# singleBlinkCricut.net
KiCad netlist of a schematic drawn in EAGLE
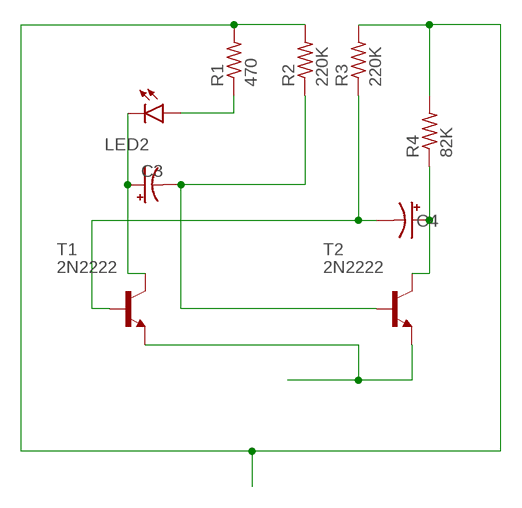
[diagram p0: schematic, sheet 1]

(export (version "E")
  (design (tool "Eeschema 10.0.6"))
  (components
    (comp (ref "C3")
      (value "CPOL-USE2.5-6")
      (footprint "eagle-import:E2,5-6")
      (libsource (lib "eagle-import") (part "CPOL-USE2.5-6"))
    )
    (comp (ref "C4")
      (value "CPOL-USE2.5-6")
      (footprint "eagle-import:E2,5-6")
      (libsource (lib "eagle-import") (part "CPOL-USE2.5-6"))
    )
    (comp (ref "LED2")
      (value "LED10MM")
      (footprint "eagle-import:LED10MM")
      (libsource (lib "eagle-import") (part "LED10MM"))
    )
    (comp (ref "R1")
      (value "470")
      (footprint "eagle-import:0411_12")
      (libsource (lib "eagle-import") (part "R-US_0411/12"))
    )
    (comp (ref "R2")
      (value "220K")
      (footprint "eagle-import:0411_12")
      (libsource (lib "eagle-import") (part "R-US_0411/12"))
    )
    (comp (ref "R3")
      (value "220K")
      (footprint "eagle-import:0411_12")
      (libsource (lib "eagle-import") (part "R-US_0411/12"))
    )
    (comp (ref "R4")
      (value "82K")
      (footprint "eagle-import:0411_12")
      (libsource (lib "eagle-import") (part "R-US_0411/12"))
    )
    (comp (ref "T1")
      (value "2N2222")
      (footprint "eagle-import:TO92-EBC-OVAL")
      (libsource (lib "eagle-import") (part "2N2222"))
    )
    (comp (ref "T2")
      (value "2N2222")
      (footprint "eagle-import:TO92-EBC-OVAL")
      (libsource (lib "eagle-import") (part "2N2222"))
    )
  )
  (nets
    (net (code "1") (name "Net-(C3-Pad-)") (class "Default")
      (node (ref "C3") (pin "-") (pinfunction "-_-") (pintype "passive"))
      (node (ref "R2") (pin "1") (pinfunction "1_1") (pintype "passive"))
      (node (ref "T2") (pin "B") (pinfunction "B_B") (pintype "passive"))
    )
    (net (code "2") (name "Net-(C4-Pad+)") (class "Default")
      (node (ref "C4") (pin "+") (pinfunction "+_+") (pintype "passive"))
      (node (ref "R4") (pin "1") (pinfunction "1_1") (pintype "passive"))
      (node (ref "T2") (pin "C") (pinfunction "C_C") (pintype "passive"))
    )
    (net (code "3") (name "Net-(C4-Pad-)") (class "Default")
      (node (ref "C4") (pin "-") (pinfunction "-_-") (pintype "passive"))
      (node (ref "R3") (pin "1") (pinfunction "1_1") (pintype "passive"))
      (node (ref "T1") (pin "B") (pinfunction "B_B") (pintype "passive"))
    )
    (net (code "4") (name "Net-(LED2-C)") (class "Default")
      (node (ref "C3") (pin "+") (pinfunction "+_+") (pintype "passive"))
      (node (ref "LED2") (pin "K") (pinfunction "C_K") (pintype "passive"))
      (node (ref "T1") (pin "C") (pinfunction "C_C") (pintype "passive"))
    )
    (net (code "5") (name "Net-(LED2-PadA)") (class "Default")
      (node (ref "LED2") (pin "A") (pinfunction "A_A") (pintype "passive"))
      (node (ref "R1") (pin "1") (pinfunction "1_1") (pintype "passive"))
    )
    (net (code "6") (name "Net-(R1-Pad2)") (class "Default")
      (node (ref "R1") (pin "2") (pinfunction "2_2") (pintype "passive"))
      (node (ref "R2") (pin "2") (pinfunction "2_2") (pintype "passive"))
      (node (ref "R3") (pin "2") (pinfunction "2_2") (pintype "passive"))
      (node (ref "R4") (pin "2") (pinfunction "2_2") (pintype "passive"))
    )
    (net (code "7") (name "Net-(T1-PadE)") (class "Default")
      (node (ref "T1") (pin "E") (pinfunction "E_E") (pintype "passive"))
      (node (ref "T2") (pin "E") (pinfunction "E_E") (pintype "passive"))
    )
  )
)
